# compact.net
KiCad netlist of a schematic drawn in EAGLE
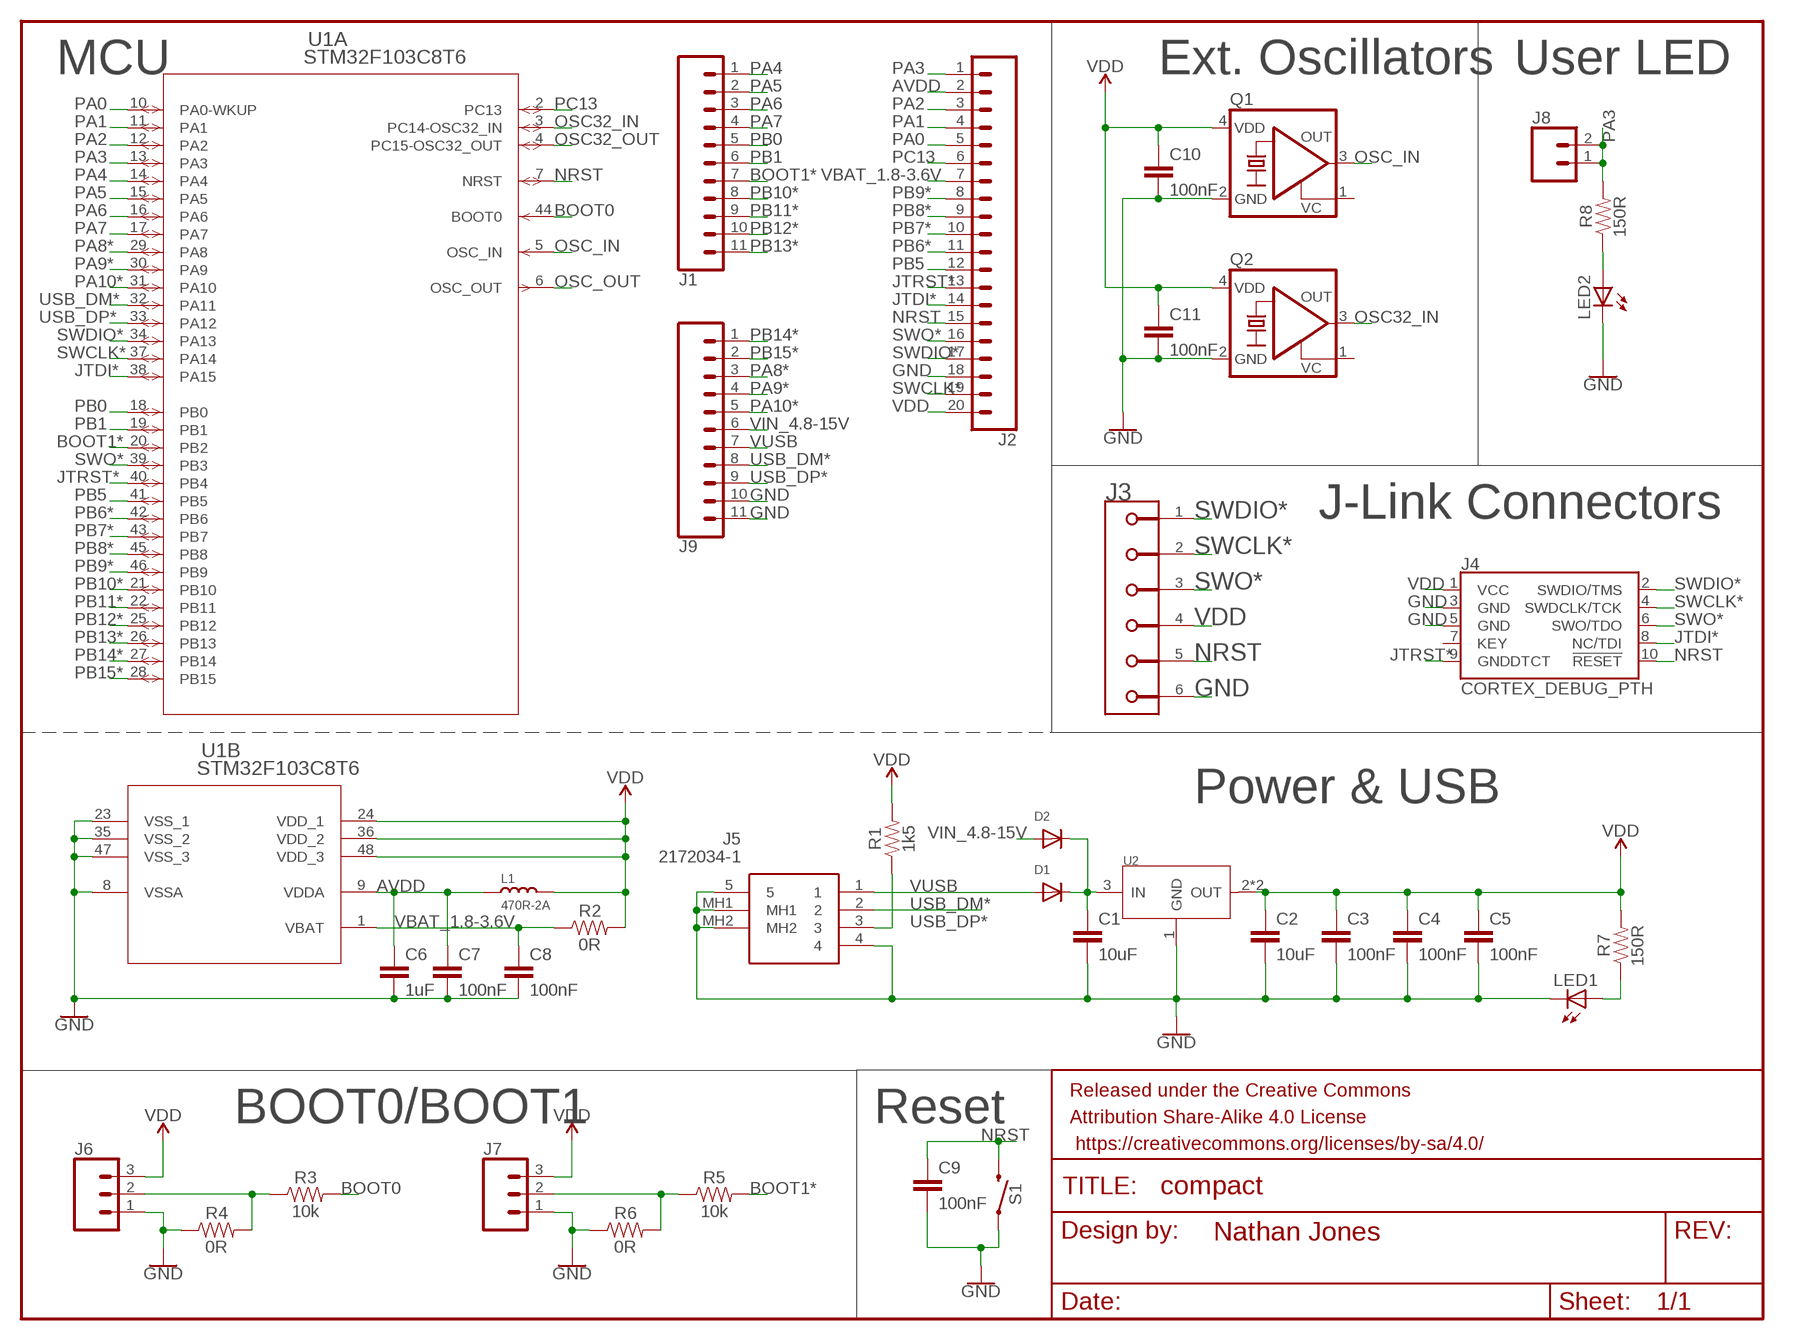
[diagram p0: schematic, sheet 1]

(export (version "E")
  (design (tool "Eeschema 10.0.6"))
  (components
    (comp (ref "C1")
      (value "10uF")
      (footprint "eagle-import:0402-TIGHT")
      (fields (field (name "LCSC_PART") "C15525"))
      (libsource (lib "eagle-import") (part "0.1UF-0402T-16V-10%"))
    )
    (comp (ref "C2")
      (value "10uF")
      (footprint "eagle-import:0402-TIGHT")
      (fields (field (name "LCSC_PART") "C15525"))
      (libsource (lib "eagle-import") (part "0.1UF-0402T-16V-10%"))
    )
    (comp (ref "C3")
      (value "100nF")
      (footprint "eagle-import:0402-TIGHT")
      (fields (field (name "LCSC_PART") "C1525"))
      (libsource (lib "eagle-import") (part "0.1UF-0402T-16V-10%"))
    )
    (comp (ref "C4")
      (value "100nF")
      (footprint "eagle-import:0402-TIGHT")
      (fields (field (name "LCSC_PART") "C1525"))
      (libsource (lib "eagle-import") (part "0.1UF-0402T-16V-10%"))
    )
    (comp (ref "C5")
      (value "100nF")
      (footprint "eagle-import:0402-TIGHT")
      (fields (field (name "LCSC_PART") "C1525"))
      (libsource (lib "eagle-import") (part "0.1UF-0402T-16V-10%"))
    )
    (comp (ref "C6")
      (value "1uF")
      (footprint "eagle-import:0402-TIGHT")
      (fields (field (name "LCSC_PART") "C52923"))
      (libsource (lib "eagle-import") (part "0.1UF-0402T-16V-10%"))
    )
    (comp (ref "C7")
      (value "100nF")
      (footprint "eagle-import:0402-TIGHT")
      (fields (field (name "LCSC_PART") "C1525"))
      (libsource (lib "eagle-import") (part "0.1UF-0402T-16V-10%"))
    )
    (comp (ref "C8")
      (value "100nF")
      (footprint "eagle-import:0402-TIGHT")
      (fields (field (name "LCSC_PART") "C1525"))
      (libsource (lib "eagle-import") (part "0.1UF-0402T-16V-10%"))
    )
    (comp (ref "C9")
      (value "100nF")
      (footprint "eagle-import:0402-TIGHT")
      (fields (field (name "LCSC_PART") "C1525"))
      (libsource (lib "eagle-import") (part "0.1UF-0402T-16V-10%"))
    )
    (comp (ref "C10")
      (value "100nF")
      (footprint "eagle-import:0402-TIGHT")
      (fields (field (name "LCSC_PART") "C1525"))
      (libsource (lib "eagle-import") (part "0.1UF-0402T-16V-10%"))
    )
    (comp (ref "C11")
      (value "100nF")
      (footprint "eagle-import:0402-TIGHT")
      (fields (field (name "LCSC_PART") "C1525"))
      (libsource (lib "eagle-import") (part "0.1UF-0402T-16V-10%"))
    )
    (comp (ref "D1")
      (value "DIODESOD-123")
      (footprint "eagle-import:SOD-123")
      (fields (field (name "LCSC_PART") "C8598"))
      (libsource (lib "eagle-import") (part "DIODESOD-123"))
    )
    (comp (ref "D2")
      (value "DIODESOD-123")
      (footprint "eagle-import:SOD-123")
      (fields (field (name "LCSC_PART") "C8598"))
      (libsource (lib "eagle-import") (part "DIODESOD-123"))
    )
    (comp (ref "FRAME2")
      (value "FRAME-LETTERNO_PACKAGE")
      (footprint "eagle-import:DUMMY")
      (fields (field (name "DESIGNER") "Nathan Jones") (field (name "DESIGNER_1") "Nathan Jones"))
      (libsource (lib "eagle-import") (part "FRAME-LETTERNO_PACKAGE"))
    )
    (comp (ref "J1")
      (value "CONN_111X11_NO_SILK")
      (footprint "eagle-import:1X11_NO_SILK")
      (libsource (lib "eagle-import") (part "CONN_111X11_NO_SILK"))
    )
    (comp (ref "J2")
      (value "CONN_20NOSILK")
      (footprint "eagle-import:1X20_NOSILK")
      (libsource (lib "eagle-import") (part "CONN_20NOSILK"))
    )
    (comp (ref "J3")
      (value "AVX_6-PIN_009159006061916_33MIL-GAP")
      (footprint "eagle-import:AVX_6-PIN_009159006061916_33MIL-GAP")
      (libsource (lib "eagle-import") (part "AVX_6-PIN_009159006061916_33MIL-GAP"))
    )
    (comp (ref "J4")
      (value "CORTEX_DEBUG_PTH")
      (footprint "eagle-import:2X5-PTH-1.27MM")
      (libsource (lib "eagle-import") (part "CORTEX_DEBUG_PTH"))
    )
    (comp (ref "J5")
      (value "2172034-1")
      (footprint "eagle-import:21720341")
      (fields (field (name "MOUSER_PART_NUMBER") "571-2172034-1"))
      (libsource (lib "eagle-import") (part "2172034-1"))
    )
    (comp (ref "J6")
      (value "CONN_031X03_NO_SILK")
      (footprint "eagle-import:1X03_NO_SILK")
      (libsource (lib "eagle-import") (part "CONN_031X03_NO_SILK"))
    )
    (comp (ref "J7")
      (value "CONN_031X03_NO_SILK")
      (footprint "eagle-import:1X03_NO_SILK")
      (libsource (lib "eagle-import") (part "CONN_031X03_NO_SILK"))
    )
    (comp (ref "J8")
      (value "CONN_021X02_NO_SILK")
      (footprint "eagle-import:1X02_NO_SILK")
      (libsource (lib "eagle-import") (part "CONN_021X02_NO_SILK"))
    )
    (comp (ref "J9")
      (value "CONN_111X11_NO_SILK")
      (footprint "eagle-import:1X11_NO_SILK")
      (libsource (lib "eagle-import") (part "CONN_111X11_NO_SILK"))
    )
    (comp (ref "L1")
      (value "470R-2A")
      (footprint "eagle-import:L0805")
      (fields (field (name "MPN") "WLB2012-471T20") (field (name "LCSC_PART") "C1015"))
      (libsource (lib "eagle-import") (part "SMD-FERRITE-BEAD-470R-2A(0805)'0805'"))
    )
    (comp (ref "LED1")
      (value "LEDCHIPLED_0603")
      (footprint "eagle-import:CHIPLED_0603")
      (fields (field (name "LCSC_PART") "C72041"))
      (libsource (lib "eagle-import") (part "LEDCHIPLED_0603"))
    )
    (comp (ref "LED2")
      (value "LEDCHIPLED_0603")
      (footprint "eagle-import:CHIPLED_0603")
      (fields (field (name "LCSC_PART") "C72038"))
      (libsource (lib "eagle-import") (part "LEDCHIPLED_0603"))
    )
    (comp (ref "Q1")
      (value "KXO-VCXO-CMOS_4")
      (footprint "eagle-import:3.2X2.5_KXO-84-TCXO")
      (fields (field (name "LCSC_PART") "C39097"))
      (libsource (lib "eagle-import") (part "KXO-VCXO-CMOS_4"))
    )
    (comp (ref "Q2")
      (value "KXO-VCXO-CMOS_4")
      (footprint "eagle-import:3.2X2.5_KXO-84-TCXO")
      (fields (field (name "LCSC_PART") "C387415"))
      (libsource (lib "eagle-import") (part "KXO-VCXO-CMOS_4"))
    )
    (comp (ref "R1")
      (value "1k5")
      (footprint "eagle-import:0402")
      (fields (field (name "LCSC_PART") "C25867"))
      (libsource (lib "eagle-import") (part "RESISTOR0402"))
    )
    (comp (ref "R2")
      (value "0R")
      (footprint "eagle-import:0402")
      (fields (field (name "LCSC_PART") "C17168"))
      (libsource (lib "eagle-import") (part "RESISTOR0402"))
    )
    (comp (ref "R3")
      (value "10k")
      (footprint "eagle-import:0402")
      (fields (field (name "LCSC_PART") "C25744"))
      (libsource (lib "eagle-import") (part "RESISTOR0402"))
    )
    (comp (ref "R4")
      (value "0R")
      (footprint "eagle-import:0402")
      (fields (field (name "LCSC_PART") "C17168"))
      (libsource (lib "eagle-import") (part "RESISTOR0402"))
    )
    (comp (ref "R5")
      (value "10k")
      (footprint "eagle-import:0402")
      (fields (field (name "LCSC_PART") "C25744"))
      (libsource (lib "eagle-import") (part "RESISTOR0402"))
    )
    (comp (ref "R6")
      (value "0R")
      (footprint "eagle-import:0402")
      (fields (field (name "LCSC_PART") "C17168"))
      (libsource (lib "eagle-import") (part "RESISTOR0402"))
    )
    (comp (ref "R7")
      (value "150R")
      (footprint "eagle-import:0402")
      (fields (field (name "LCSC_PART") "C25082"))
      (libsource (lib "eagle-import") (part "RESISTOR0402"))
    )
    (comp (ref "R8")
      (value "150R")
      (footprint "eagle-import:0402")
      (fields (field (name "LCSC_PART") "C25082"))
      (libsource (lib "eagle-import") (part "RESISTOR0402"))
    )
    (comp (ref "S1")
      (value "MOMENTARY-SWITCH-SPST-SMD-5.2-REDUNDANT")
      (footprint "eagle-import:TACTILE_SWITCH_SMD_5.2MM")
      (fields (field (name "LCSC_PART") "C318884"))
      (libsource (lib "eagle-import") (part "MOMENTARY-SWITCH-SPST-SMD-5.2-REDUNDANT"))
    )
    (comp (ref "U1")
      (value "STM32F103C8T6")
      (footprint "eagle-import:LQFP48-7X7MM")
      (fields
        (field (name "LCSC_PART") "C94046")
        (field (name "COPYRIGHT") "Copyright (C) 2018 Accelerated Designs. All rights reserved")
      )
      (libsource (lib "eagle-import") (part "STM32F103C8T6"))
    )
    (comp (ref "U2")
      (value "CJT1117-3.3-SOT223")
      (footprint "eagle-import:SOT-223")
      (fields (field (name "MPN") "CJT1117-3.3") (field (name "LCSC_PART") "C6186"))
      (libsource (lib "eagle-import") (part "PMIC-CJT1117-3.3(SOT223)"))
    )
  )
  (nets
    (net (code "1") (name "/AVDD") (class "Default")
      (node (ref "C6") (pin "1") (pinfunction "1_1") (pintype "passive"))
      (node (ref "C7") (pin "1") (pinfunction "1_1") (pintype "passive"))
      (node (ref "J2") (pin "2") (pinfunction "2_2") (pintype "passive"))
      (node (ref "L1") (pin "1") (pinfunction "1_1") (pintype "passive"))
      (node (ref "U1") (pin "9") (pinfunction "VDDA_9") (pintype "power_in"))
    )
    (net (code "2") (name "/BOOT0") (class "Default")
      (node (ref "R3") (pin "2") (pinfunction "2_2") (pintype "passive"))
      (node (ref "U1") (pin "44") (pinfunction "BOOT0_44") (pintype "input"))
    )
    (net (code "3") (name "/BOOT1*") (class "Default")
      (node (ref "J1") (pin "7") (pinfunction "7_7") (pintype "passive"))
      (node (ref "R5") (pin "2") (pinfunction "2_2") (pintype "passive"))
      (node (ref "U1") (pin "20") (pinfunction "PB2_20") (pintype "bidirectional"))
    )
    (net (code "4") (name "/JTDI*") (class "Default")
      (node (ref "J2") (pin "14") (pinfunction "14_14") (pintype "passive"))
      (node (ref "J4") (pin "8") (pinfunction "NC/TDI_8") (pintype "bidirectional"))
      (node (ref "U1") (pin "38") (pinfunction "PA15_38") (pintype "bidirectional"))
    )
    (net (code "5") (name "/JTRST*") (class "Default")
      (node (ref "J2") (pin "13") (pinfunction "13_13") (pintype "passive"))
      (node (ref "J4") (pin "9") (pinfunction "GNDDTCT_9") (pintype "bidirectional"))
      (node (ref "U1") (pin "40") (pinfunction "PB4_40") (pintype "bidirectional"))
    )
    (net (code "6") (name "/NRST") (class "Default")
      (node (ref "C9") (pin "1") (pinfunction "1_1") (pintype "passive"))
      (node (ref "J2") (pin "15") (pinfunction "15_15") (pintype "passive"))
      (node (ref "J3") (pin "5") (pinfunction "5_5") (pintype "bidirectional"))
      (node (ref "J4") (pin "10") (pinfunction "~{RESET}_10") (pintype "bidirectional"))
      (node (ref "S1") (pin "3") (pinfunction "2_3") (pintype "passive"))
      (node (ref "S1") (pin "4") (pinfunction "2_4") (pintype "passive"))
      (node (ref "U1") (pin "7") (pinfunction "NRST_7") (pintype "bidirectional"))
    )
    (net (code "7") (name "/OSC32_IN") (class "Default")
      (node (ref "Q2") (pin "3") (pinfunction "OUT_3") (pintype "output"))
      (node (ref "U1") (pin "3") (pinfunction "PC14-OSC32_IN_3") (pintype "bidirectional"))
    )
    (net (code "8") (name "/OSC32_OUT") (class "Default")
      (node (ref "U1") (pin "4") (pinfunction "PC15-OSC32_OUT_4") (pintype "bidirectional"))
    )
    (net (code "9") (name "/OSC_IN") (class "Default")
      (node (ref "Q1") (pin "3") (pinfunction "OUT_3") (pintype "output"))
      (node (ref "U1") (pin "5") (pinfunction "OSC_IN_5") (pintype "input"))
    )
    (net (code "10") (name "/OSC_OUT") (class "Default")
      (node (ref "U1") (pin "6") (pinfunction "OSC_OUT_6") (pintype "output"))
    )
    (net (code "11") (name "/PA0") (class "Default")
      (node (ref "J2") (pin "5") (pinfunction "5_5") (pintype "passive"))
      (node (ref "U1") (pin "10") (pinfunction "PA0-WKUP_10") (pintype "bidirectional"))
    )
    (net (code "12") (name "/PA1") (class "Default")
      (node (ref "J2") (pin "4") (pinfunction "4_4") (pintype "passive"))
      (node (ref "U1") (pin "11") (pinfunction "PA1_11") (pintype "bidirectional"))
    )
    (net (code "13") (name "/PA2") (class "Default")
      (node (ref "J2") (pin "3") (pinfunction "3_3") (pintype "passive"))
      (node (ref "U1") (pin "12") (pinfunction "PA2_12") (pintype "bidirectional"))
    )
    (net (code "14") (name "/PA3") (class "Default")
      (node (ref "J2") (pin "1") (pinfunction "1_1") (pintype "passive"))
      (node (ref "J8") (pin "1") (pinfunction "1_1") (pintype "passive"))
      (node (ref "J8") (pin "2") (pinfunction "2_2") (pintype "passive"))
      (node (ref "R8") (pin "2") (pinfunction "2_2") (pintype "passive"))
      (node (ref "U1") (pin "13") (pinfunction "PA3_13") (pintype "bidirectional"))
    )
    (net (code "15") (name "/PA4") (class "Default")
      (node (ref "J1") (pin "1") (pinfunction "1_1") (pintype "passive"))
      (node (ref "U1") (pin "14") (pinfunction "PA4_14") (pintype "bidirectional"))
    )
    (net (code "16") (name "/PA5") (class "Default")
      (node (ref "J1") (pin "2") (pinfunction "2_2") (pintype "passive"))
      (node (ref "U1") (pin "15") (pinfunction "PA5_15") (pintype "bidirectional"))
    )
    (net (code "17") (name "/PA6") (class "Default")
      (node (ref "J1") (pin "3") (pinfunction "3_3") (pintype "passive"))
      (node (ref "U1") (pin "16") (pinfunction "PA6_16") (pintype "bidirectional"))
    )
    (net (code "18") (name "/PA7") (class "Default")
      (node (ref "J1") (pin "4") (pinfunction "4_4") (pintype "passive"))
      (node (ref "U1") (pin "17") (pinfunction "PA7_17") (pintype "bidirectional"))
    )
    (net (code "19") (name "/PA8*") (class "Default")
      (node (ref "J9") (pin "3") (pinfunction "3_3") (pintype "passive"))
      (node (ref "U1") (pin "29") (pinfunction "PA8_29") (pintype "bidirectional"))
    )
    (net (code "20") (name "/PA9*") (class "Default")
      (node (ref "J9") (pin "4") (pinfunction "4_4") (pintype "passive"))
      (node (ref "U1") (pin "30") (pinfunction "PA9_30") (pintype "bidirectional"))
    )
    (net (code "21") (name "/PA10*") (class "Default")
      (node (ref "J9") (pin "5") (pinfunction "5_5") (pintype "passive"))
      (node (ref "U1") (pin "31") (pinfunction "PA10_31") (pintype "bidirectional"))
    )
    (net (code "22") (name "/PB0") (class "Default")
      (node (ref "J1") (pin "5") (pinfunction "5_5") (pintype "passive"))
      (node (ref "U1") (pin "18") (pinfunction "PB0_18") (pintype "bidirectional"))
    )
    (net (code "23") (name "/PB1") (class "Default")
      (node (ref "J1") (pin "6") (pinfunction "6_6") (pintype "passive"))
      (node (ref "U1") (pin "19") (pinfunction "PB1_19") (pintype "bidirectional"))
    )
    (net (code "24") (name "/PB5") (class "Default")
      (node (ref "J2") (pin "12") (pinfunction "12_12") (pintype "passive"))
      (node (ref "U1") (pin "41") (pinfunction "PB5_41") (pintype "bidirectional"))
    )
    (net (code "25") (name "/PB6*") (class "Default")
      (node (ref "J2") (pin "11") (pinfunction "11_11") (pintype "passive"))
      (node (ref "U1") (pin "42") (pinfunction "PB6_42") (pintype "bidirectional"))
    )
    (net (code "26") (name "/PB7*") (class "Default")
      (node (ref "J2") (pin "10") (pinfunction "10_10") (pintype "passive"))
      (node (ref "U1") (pin "43") (pinfunction "PB7_43") (pintype "bidirectional"))
    )
    (net (code "27") (name "/PB8*") (class "Default")
      (node (ref "J2") (pin "9") (pinfunction "9_9") (pintype "passive"))
      (node (ref "U1") (pin "45") (pinfunction "PB8_45") (pintype "bidirectional"))
    )
    (net (code "28") (name "/PB9*") (class "Default")
      (node (ref "J2") (pin "8") (pinfunction "8_8") (pintype "passive"))
      (node (ref "U1") (pin "46") (pinfunction "PB9_46") (pintype "bidirectional"))
    )
    (net (code "29") (name "/PB10*") (class "Default")
      (node (ref "J1") (pin "8") (pinfunction "8_8") (pintype "passive"))
      (node (ref "U1") (pin "21") (pinfunction "PB10_21") (pintype "bidirectional"))
    )
    (net (code "30") (name "/PB11*") (class "Default")
      (node (ref "J1") (pin "9") (pinfunction "9_9") (pintype "passive"))
      (node (ref "U1") (pin "22") (pinfunction "PB11_22") (pintype "bidirectional"))
    )
    (net (code "31") (name "/PB12*") (class "Default")
      (node (ref "J1") (pin "10") (pinfunction "10_10") (pintype "passive"))
      (node (ref "U1") (pin "25") (pinfunction "PB12_25") (pintype "bidirectional"))
    )
    (net (code "32") (name "/PB13*") (class "Default")
      (node (ref "J1") (pin "11") (pinfunction "11_11") (pintype "passive"))
      (node (ref "U1") (pin "26") (pinfunction "PB13_26") (pintype "bidirectional"))
    )
    (net (code "33") (name "/PB14*") (class "Default")
      (node (ref "J9") (pin "1") (pinfunction "1_1") (pintype "passive"))
      (node (ref "U1") (pin "27") (pinfunction "PB14_27") (pintype "bidirectional"))
    )
    (net (code "34") (name "/PB15*") (class "Default")
      (node (ref "J9") (pin "2") (pinfunction "2_2") (pintype "passive"))
      (node (ref "U1") (pin "28") (pinfunction "PB15_28") (pintype "bidirectional"))
    )
    (net (code "35") (name "/PC13") (class "Default")
      (node (ref "J2") (pin "6") (pinfunction "6_6") (pintype "passive"))
      (node (ref "U1") (pin "2") (pinfunction "PC13_2") (pintype "bidirectional"))
    )
    (net (code "36") (name "/SWCLK*") (class "Default")
      (node (ref "J2") (pin "19") (pinfunction "19_19") (pintype "passive"))
      (node (ref "J3") (pin "2") (pinfunction "2_2") (pintype "bidirectional"))
      (node (ref "J4") (pin "4") (pinfunction "SWDCLK/TCK_4") (pintype "bidirectional"))
      (node (ref "U1") (pin "37") (pinfunction "PA14_37") (pintype "bidirectional"))
    )
    (net (code "37") (name "/SWDIO*") (class "Default")
      (node (ref "J2") (pin "17") (pinfunction "17_17") (pintype "passive"))
      (node (ref "J3") (pin "1") (pinfunction "1_1") (pintype "bidirectional"))
      (node (ref "J4") (pin "2") (pinfunction "SWDIO/TMS_2") (pintype "bidirectional"))
      (node (ref "U1") (pin "34") (pinfunction "PA13_34") (pintype "bidirectional"))
    )
    (net (code "38") (name "/SWO*") (class "Default")
      (node (ref "J2") (pin "16") (pinfunction "16_16") (pintype "passive"))
      (node (ref "J3") (pin "3") (pinfunction "3_3") (pintype "bidirectional"))
      (node (ref "J4") (pin "6") (pinfunction "SWO/TDO_6") (pintype "bidirectional"))
      (node (ref "U1") (pin "39") (pinfunction "PB3_39") (pintype "bidirectional"))
    )
    (net (code "39") (name "/USB_DM*") (class "Default")
      (node (ref "J5") (pin "2") (pinfunction "2_2") (pintype "bidirectional"))
      (node (ref "J9") (pin "8") (pinfunction "8_8") (pintype "passive"))
      (node (ref "U1") (pin "32") (pinfunction "PA11_32") (pintype "bidirectional"))
    )
    (net (code "40") (name "/USB_DP*") (class "Default")
      (node (ref "J5") (pin "3") (pinfunction "3_3") (pintype "bidirectional"))
      (node (ref "J9") (pin "9") (pinfunction "9_9") (pintype "passive"))
      (node (ref "R1") (pin "1") (pinfunction "1_1") (pintype "passive"))
      (node (ref "U1") (pin "33") (pinfunction "PA12_33") (pintype "bidirectional"))
    )
    (net (code "41") (name "/VBAT_1.8-3.6V") (class "Default")
      (node (ref "C8") (pin "1") (pinfunction "1_1") (pintype "passive"))
      (node (ref "J2") (pin "7") (pinfunction "7_7") (pintype "passive"))
      (node (ref "R2") (pin "1") (pinfunction "1_1") (pintype "passive"))
      (node (ref "U1") (pin "1") (pinfunction "VBAT_1") (pintype "power_in"))
    )
    (net (code "42") (name "/VIN_4.8-15V") (class "Default")
      (node (ref "D2") (pin "A") (pinfunction "A_A") (pintype "passive"))
      (node (ref "J9") (pin "6") (pinfunction "6_6") (pintype "passive"))
    )
    (net (code "43") (name "/VUSB") (class "Default")
      (node (ref "D1") (pin "A") (pinfunction "A_A") (pintype "passive"))
      (node (ref "J5") (pin "1") (pinfunction "1_1") (pintype "bidirectional"))
      (node (ref "J9") (pin "7") (pinfunction "7_7") (pintype "passive"))
    )
    (net (code "44") (name "GND") (class "Default")
      (node (ref "C1") (pin "2") (pinfunction "2_2") (pintype "passive"))
      (node (ref "C10") (pin "2") (pinfunction "2_2") (pintype "passive"))
      (node (ref "C11") (pin "2") (pinfunction "2_2") (pintype "passive"))
      (node (ref "C2") (pin "2") (pinfunction "2_2") (pintype "passive"))
      (node (ref "C3") (pin "2") (pinfunction "2_2") (pintype "passive"))
      (node (ref "C4") (pin "2") (pinfunction "2_2") (pintype "passive"))
      (node (ref "C5") (pin "2") (pinfunction "2_2") (pintype "passive"))
      (node (ref "C6") (pin "2") (pinfunction "2_2") (pintype "passive"))
      (node (ref "C7") (pin "2") (pinfunction "2_2") (pintype "passive"))
      (node (ref "C8") (pin "2") (pinfunction "2_2") (pintype "passive"))
      (node (ref "C9") (pin "2") (pinfunction "2_2") (pintype "passive"))
      (node (ref "J2") (pin "18") (pinfunction "18_18") (pintype "passive"))
      (node (ref "J3") (pin "6") (pinfunction "6_6") (pintype "bidirectional"))
      (node (ref "J4") (pin "3") (pinfunction "GND_3") (pintype "bidirectional"))
      (node (ref "J4") (pin "5") (pinfunction "GND_5") (pintype "bidirectional"))
      (node (ref "J5") (pin "4") (pinfunction "4_4") (pintype "bidirectional"))
      (node (ref "J5") (pin "5") (pinfunction "5_5") (pintype "bidirectional"))
      (node (ref "J5") (pin "MH1") (pinfunction "MH1_MH1") (pintype "bidirectional"))
      (node (ref "J5") (pin "MH2") (pinfunction "MH2_MH2") (pintype "bidirectional"))
      (node (ref "J6") (pin "1") (pinfunction "1_1") (pintype "passive"))
      (node (ref "J7") (pin "1") (pinfunction "1_1") (pintype "passive"))
      (node (ref "J9") (pin "10") (pinfunction "10_10") (pintype "passive"))
      (node (ref "J9") (pin "11") (pinfunction "11_11") (pintype "passive"))
      (node (ref "LED1") (pin "C") (pinfunction "C_C") (pintype "passive"))
      (node (ref "LED2") (pin "C") (pinfunction "C_C") (pintype "passive"))
      (node (ref "Q1") (pin "2") (pinfunction "GND_2") (pintype "power_in"))
      (node (ref "Q2") (pin "2") (pinfunction "GND_2") (pintype "power_in"))
      (node (ref "R4") (pin "1") (pinfunction "1_1") (pintype "passive"))
      (node (ref "R6") (pin "1") (pinfunction "1_1") (pintype "passive"))
      (node (ref "S1") (pin "1") (pinfunction "1_1") (pintype "passive"))
      (node (ref "S1") (pin "2") (pinfunction "1_2") (pintype "passive"))
      (node (ref "U1") (pin "23") (pinfunction "VSS_1_23") (pintype "power_in"))
      (node (ref "U1") (pin "35") (pinfunction "VSS_2_35") (pintype "power_in"))
      (node (ref "U1") (pin "47") (pinfunction "VSS_3_47") (pintype "power_in"))
      (node (ref "U1") (pin "8") (pinfunction "VSSA_8") (pintype "power_in"))
      (node (ref "U2") (pin "1") (pinfunction "GND_1") (pintype "bidirectional"))
    )
    (net (code "45") (name "Net-(J6-Pad2)") (class "Default")
      (node (ref "J6") (pin "2") (pinfunction "2_2") (pintype "passive"))
      (node (ref "R3") (pin "1") (pinfunction "1_1") (pintype "passive"))
      (node (ref "R4") (pin "2") (pinfunction "2_2") (pintype "passive"))
    )
    (net (code "46") (name "Net-(J7-Pad2)") (class "Default")
      (node (ref "J7") (pin "2") (pinfunction "2_2") (pintype "passive"))
      (node (ref "R5") (pin "1") (pinfunction "1_1") (pintype "passive"))
      (node (ref "R6") (pin "2") (pinfunction "2_2") (pintype "passive"))
    )
    (net (code "47") (name "Net-(LED1-PadA)") (class "Default")
      (node (ref "LED1") (pin "A") (pinfunction "A_A") (pintype "passive"))
      (node (ref "R7") (pin "1") (pinfunction "1_1") (pintype "passive"))
    )
    (net (code "48") (name "Net-(LED2-PadA)") (class "Default")
      (node (ref "LED2") (pin "A") (pinfunction "A_A") (pintype "passive"))
      (node (ref "R8") (pin "1") (pinfunction "1_1") (pintype "passive"))
    )
    (net (code "49") (name "Net-(U2-IN)") (class "Default")
      (node (ref "C1") (pin "1") (pinfunction "1_1") (pintype "passive"))
      (node (ref "D1") (pin "C") (pinfunction "C_C") (pintype "passive"))
      (node (ref "D2") (pin "C") (pinfunction "C_C") (pintype "passive"))
      (node (ref "U2") (pin "3") (pinfunction "IN_3") (pintype "bidirectional"))
    )
    (net (code "50") (name "VDD") (class "Default")
      (node (ref "C10") (pin "1") (pinfunction "1_1") (pintype "passive"))
      (node (ref "C11") (pin "1") (pinfunction "1_1") (pintype "passive"))
      (node (ref "C2") (pin "1") (pinfunction "1_1") (pintype "passive"))
      (node (ref "C3") (pin "1") (pinfunction "1_1") (pintype "passive"))
      (node (ref "C4") (pin "1") (pinfunction "1_1") (pintype "passive"))
      (node (ref "C5") (pin "1") (pinfunction "1_1") (pintype "passive"))
      (node (ref "J2") (pin "20") (pinfunction "20_20") (pintype "passive"))
      (node (ref "J3") (pin "4") (pinfunction "4_4") (pintype "bidirectional"))
      (node (ref "J4") (pin "1") (pinfunction "VCC_1") (pintype "bidirectional"))
      (node (ref "J6") (pin "3") (pinfunction "3_3") (pintype "passive"))
      (node (ref "J7") (pin "3") (pinfunction "3_3") (pintype "passive"))
      (node (ref "L1") (pin "2") (pinfunction "2_2") (pintype "passive"))
      (node (ref "Q1") (pin "4") (pinfunction "VDD_4") (pintype "power_in"))
      (node (ref "Q2") (pin "4") (pinfunction "VDD_4") (pintype "power_in"))
      (node (ref "R1") (pin "2") (pinfunction "2_2") (pintype "passive"))
      (node (ref "R2") (pin "2") (pinfunction "2_2") (pintype "passive"))
      (node (ref "R7") (pin "2") (pinfunction "2_2") (pintype "passive"))
      (node (ref "U1") (pin "24") (pinfunction "VDD_1_24") (pintype "power_in"))
      (node (ref "U1") (pin "36") (pinfunction "VDD_2_36") (pintype "power_in"))
      (node (ref "U1") (pin "48") (pinfunction "VDD_3_48") (pintype "power_in"))
      (node (ref "U2") (pin "2") (pinfunction "OUT_2") (pintype "bidirectional"))
      (node (ref "U2") (pin "TER") (pinfunction "OUT_TER") (pintype "bidirectional"))
    )
    (net (code "51") (name "unconnected-(J4-KEY-Pad7)") (class "Default")
      (node (ref "J4") (pin "7") (pinfunction "KEY_7") (pintype "bidirectional"))
    )
    (net (code "52") (name "unconnected-(Q1-VC-Pad1)") (class "Default")
      (node (ref "Q1") (pin "1") (pinfunction "VC_1") (pintype "input"))
    )
    (net (code "53") (name "unconnected-(Q2-VC-Pad1)") (class "Default")
      (node (ref "Q2") (pin "1") (pinfunction "VC_1") (pintype "input"))
    )
  )
)
